# H0FR8.net
KiCad netlist of a schematic drawn in EAGLE
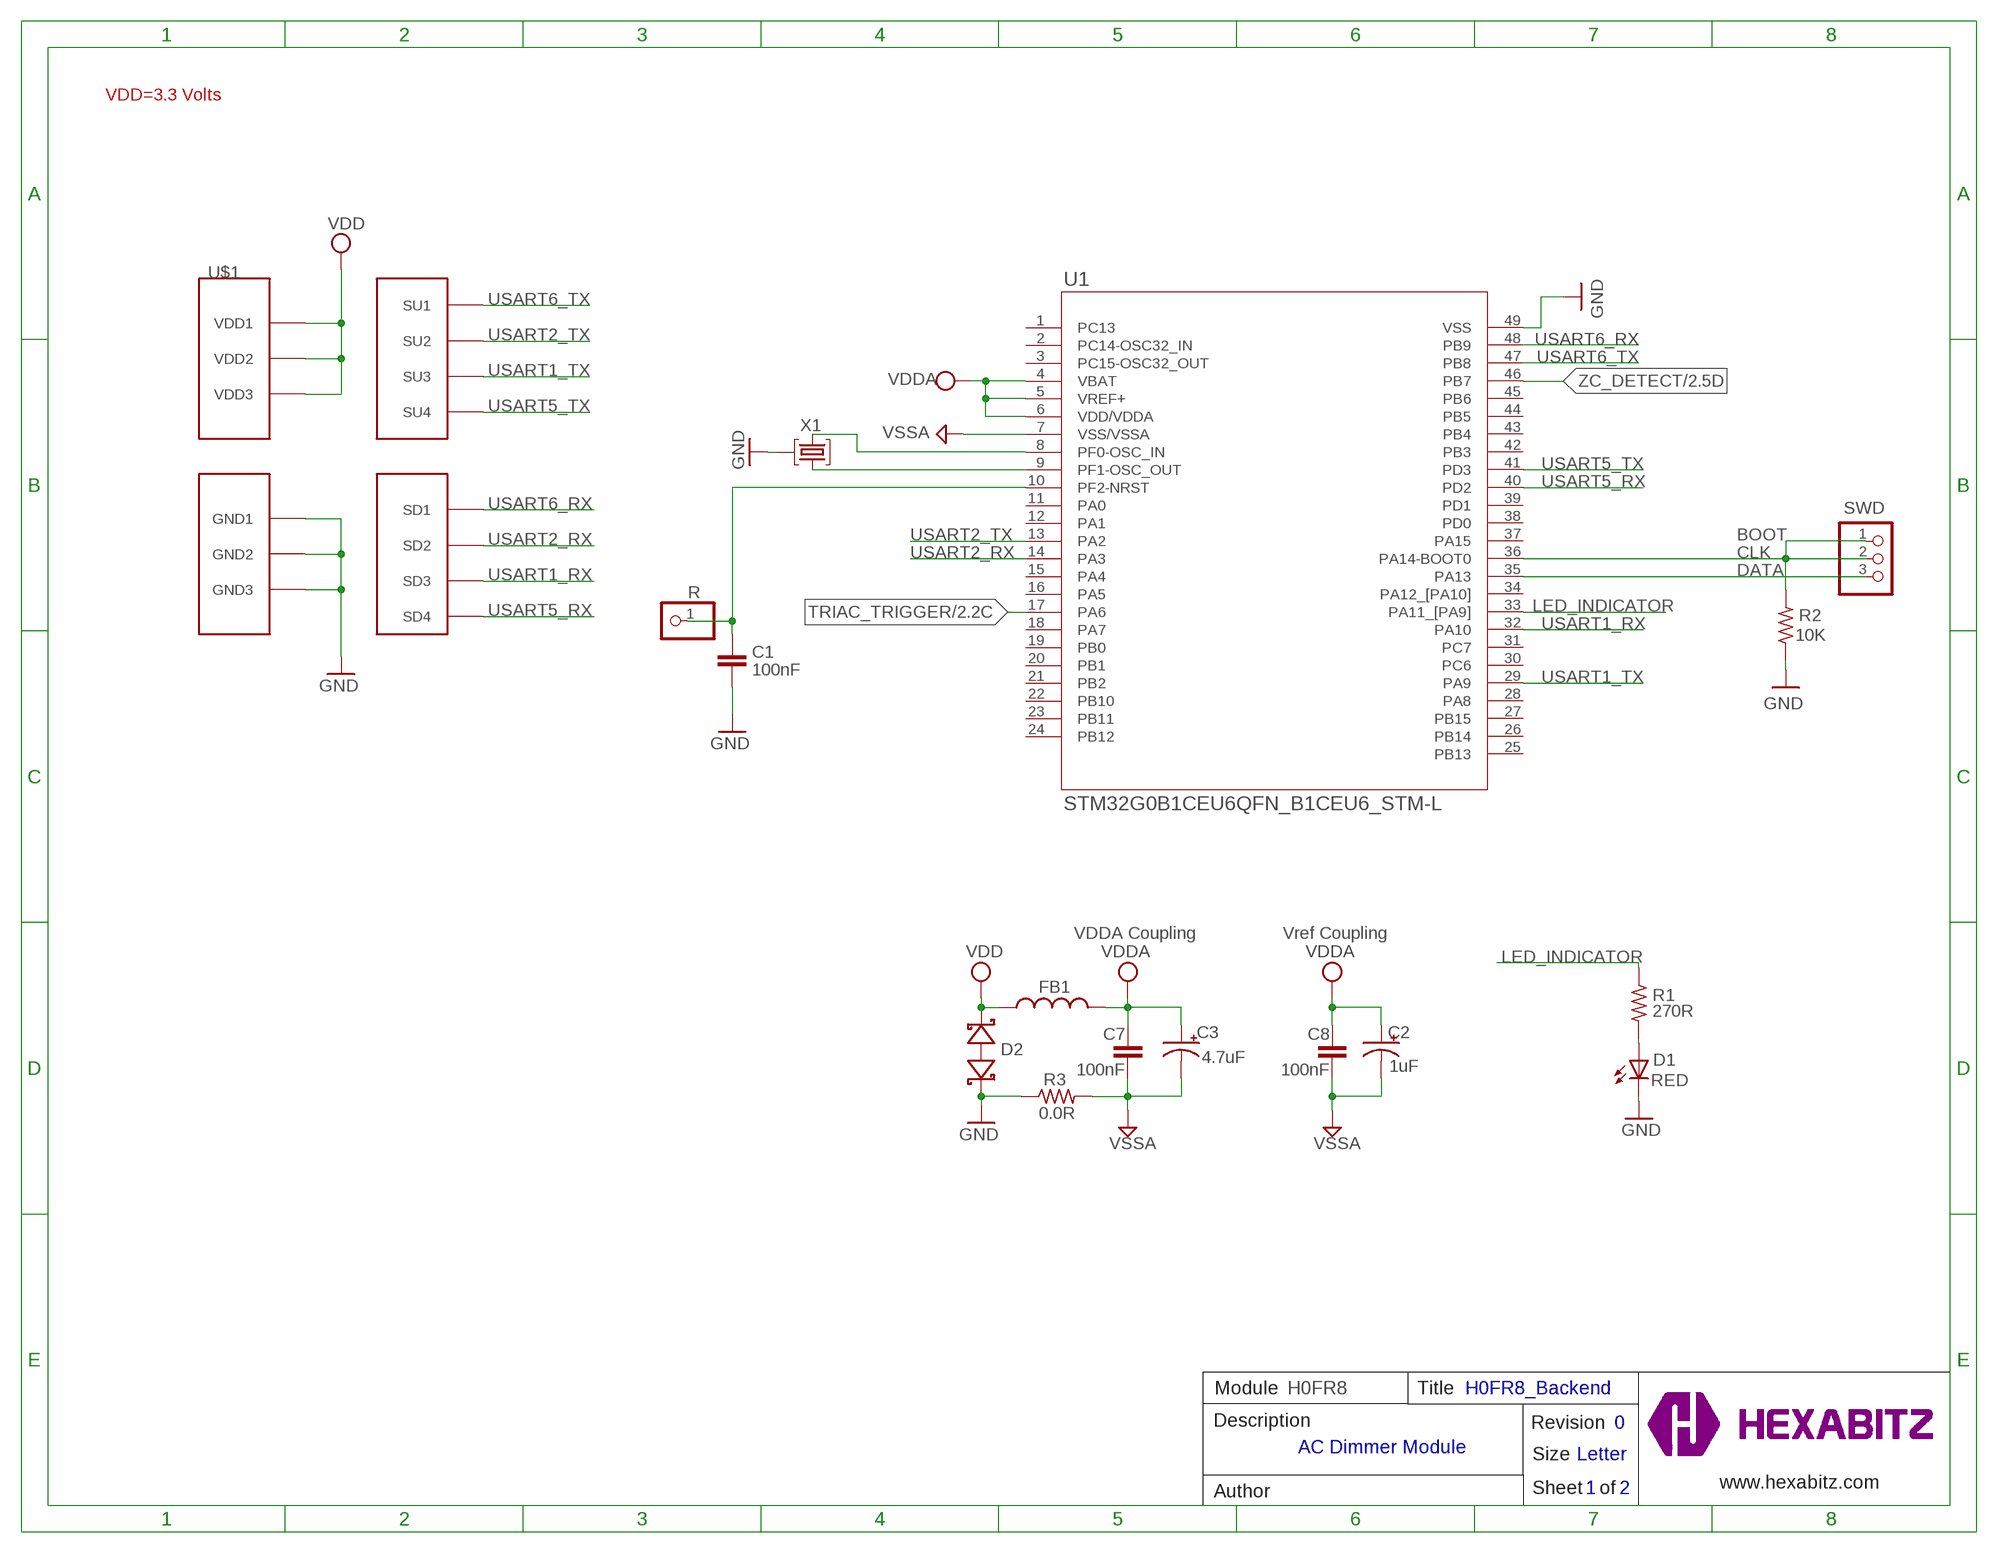
[diagram p0: schematic, sheet 1]
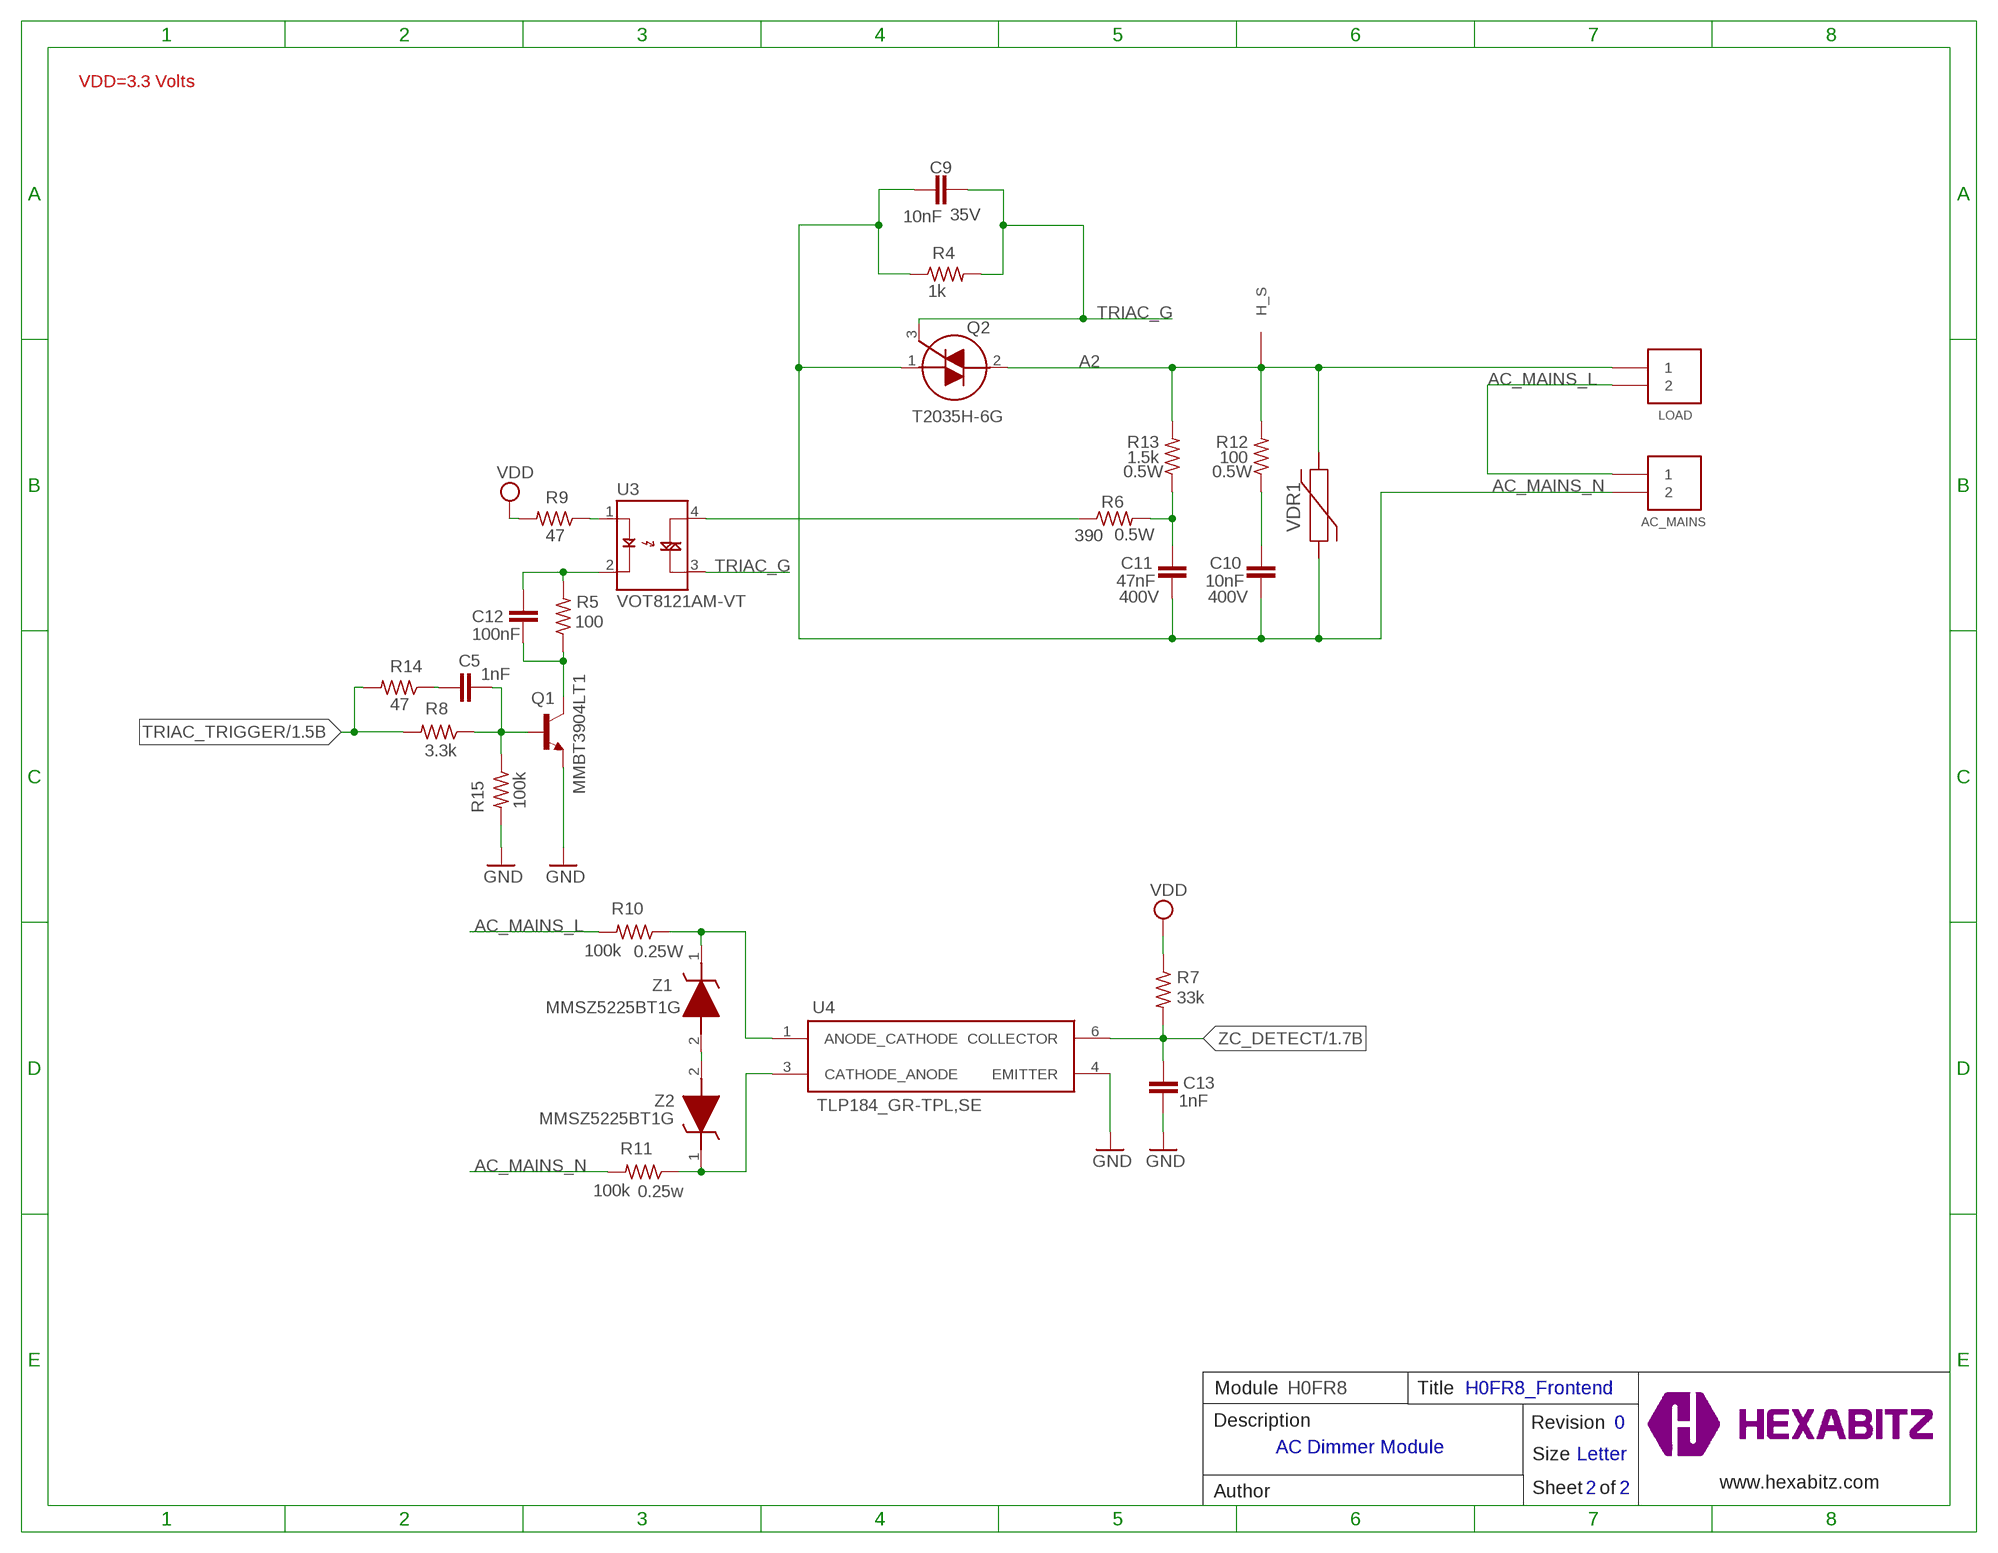
[diagram p1: schematic, sheet 2]

(export (version "E")
  (design (tool "Eeschema 10.0.6"))
  (components
    (comp (ref "AC_MAINS")
      (value "1546111-2")
      (footprint "eagle-import:1546111-2")
      (libsource (lib "eagle-import") (part "1546111-2"))
    )
    (comp (ref "C5")
      (value "1nF")
      (footprint "eagle-import:C-0603")
      (libsource (lib "eagle-import") (part "C-0603"))
    )
    (comp (ref "C9")
      (value "10nF")
      (footprint "eagle-import:C-0603")
      (fields (field (name "VOLTAGE_RATING") "35V"))
      (libsource (lib "eagle-import") (part "C-0603"))
    )
    (comp (ref "C10")
      (value "10nF")
      (footprint "eagle-import:C-0805")
      (fields (field (name "MPN") "C2012X7T2W103M085AA") (field (name "VOLTAGE_RATING") "400V"))
      (libsource (lib "eagle-import") (part "C-0805"))
    )
    (comp (ref "C11")
      (value "47nF")
      (footprint "eagle-import:C-0805")
      (fields (field (name "MPN") "C2012X7T2W473K125AA") (field (name "VOLTAGE_RATING") "400V"))
      (libsource (lib "eagle-import") (part "C-0805"))
    )
    (comp (ref "C12")
      (value "100nF")
      (footprint "eagle-import:C-0603")
      (libsource (lib "eagle-import") (part "C-0603"))
    )
    (comp (ref "C13")
      (value "1nF")
      (footprint "eagle-import:C-0603")
      (libsource (lib "eagle-import") (part "C-0603"))
    )
    (comp (ref "LOAD")
      (value "1546111-2")
      (footprint "eagle-import:1546111-2")
      (libsource (lib "eagle-import") (part "1546111-2"))
    )
    (comp (ref "Q1")
      (value "MMBT3904LT1")
      (footprint "eagle-import:MMBT3904LT1")
      (fields
        (field (name "MFN") "ON Semiconductor")
        (field (name "MPN") "MMBT3904LT1G")
        (field (name "OCTOPART_ID") "0bb6c2bc2200d471")
        (field (name "OCTOPART_URL") "http://octopart.com/mmbt3904lt1g-on+semiconductor-3280")
        (field (name "POLARITY") "NPN")
        (field (name "POWER_DISSIPATION") "0.225 W")
        (field (name "VOLTAGE_RATING_DC") "40.0 V")
      )
      (libsource (lib "eagle-import") (part "MMBT3904LT1"))
    )
    (comp (ref "Q2")
      (value "T2035H-6G")
      (footprint "eagle-import:T2035H6G")
      (fields (field (name "MOUSER_PART_NUMBER") "511-T2035H-6G"))
      (libsource (lib "eagle-import") (part "T2035H-6G"))
    )
    (comp (ref "R4")
      (value "1k")
      (footprint "eagle-import:R-0603")
      (libsource (lib "eagle-import") (part "R-0603"))
    )
    (comp (ref "R5")
      (value "100")
      (footprint "eagle-import:R-0603")
      (fields
        (field (name "MFN") "Yageo")
        (field (name "MPN") "RC0402FR-07100RL")
        (field (name "OCTOPART_URL") "https://octopart.com/crcw0603110rfkea-vishay-39455532")
        (field (name "RESISTANCE") "110.0 Ω")
        (field (name "TOLERANCE") "±1%")
      )
      (libsource (lib "eagle-import") (part "R-0603"))
    )
    (comp (ref "R6")
      (value "390")
      (footprint "eagle-import:R-0805")
      (fields (field (name "MPN") "ERJ-P06J391V") (field (name "POWER") "0.5W"))
      (libsource (lib "eagle-import") (part "R-0805"))
    )
    (comp (ref "R7")
      (value "33k")
      (footprint "eagle-import:R-0603")
      (fields
        (field (name "MFN") "Yageo")
        (field (name "MPN") "RC0402FR-07100RL")
        (field (name "OCTOPART_URL") "https://octopart.com/crcw0603110rfkea-vishay-39455532")
        (field (name "RESISTANCE") "110.0 Ω")
        (field (name "TOLERANCE") "±1%")
      )
      (libsource (lib "eagle-import") (part "R-0603"))
    )
    (comp (ref "R8")
      (value "3.3k")
      (footprint "eagle-import:R-0603")
      (fields
        (field (name "MFN") "Yageo")
        (field (name "MPN") "RC0603JR-070RL")
        (field (name "OCTOPART_URL") "https://octopart.com/crcw06032k40jnea-vishay-40298967")
        (field (name "RESISTANCE") "2400.0 Ω")
        (field (name "TOLERANCE") "±5%")
      )
      (libsource (lib "eagle-import") (part "R-0603"))
    )
    (comp (ref "R9")
      (value "47")
      (footprint "eagle-import:R-0603")
      (fields
        (field (name "MFN") "Yageo")
        (field (name "MPN") "RC0402FR-07100RL")
        (field (name "OCTOPART_URL") "https://octopart.com/crcw0603110rfkea-vishay-39455532")
        (field (name "RESISTANCE") "110.0 Ω")
        (field (name "TOLERANCE") "±1%")
      )
      (libsource (lib "eagle-import") (part "R-0603"))
    )
    (comp (ref "R10")
      (value "100k")
      (footprint "eagle-import:R-0805")
      (fields
        (field (name "MFN") "Yageo")
        (field (name "MPN") "RC0603JR-070RL")
        (field (name "OCTOPART_URL") "https://octopart.com/crcw06032k40jnea-vishay-40298967")
        (field (name "POWER") "0.25W")
        (field (name "RESISTANCE") "2400.0 Ω")
        (field (name "TOLERANCE") "±5%")
      )
      (libsource (lib "eagle-import") (part "R-0805"))
    )
    (comp (ref "R11")
      (value "100k")
      (footprint "eagle-import:R-0805")
      (fields (field (name "MPN") "ERJ-P06J104V") (field (name "POWER") "0.25w"))
      (libsource (lib "eagle-import") (part "R-0805"))
    )
    (comp (ref "R12")
      (value "100")
      (footprint "eagle-import:R-0805")
      (fields (field (name "MPN") "ERJ-P06J101V") (field (name "POWER") "0.5W"))
      (libsource (lib "eagle-import") (part "R-0805"))
    )
    (comp (ref "R13")
      (value "1.5k")
      (footprint "eagle-import:R-0805")
      (fields (field (name "MPN") "ERJ-P06J152V") (field (name "POWER") "0.5W"))
      (libsource (lib "eagle-import") (part "R-0805"))
    )
    (comp (ref "R14")
      (value "47")
      (footprint "eagle-import:R-0603")
      (fields
        (field (name "MFN") "Yageo")
        (field (name "MPN") "RC0402FR-07100RL")
        (field (name "OCTOPART_URL") "https://octopart.com/crcw0603110rfkea-vishay-39455532")
        (field (name "RESISTANCE") "110.0 Ω")
        (field (name "TOLERANCE") "±1%")
      )
      (libsource (lib "eagle-import") (part "R-0603"))
    )
    (comp (ref "R15")
      (value "100k")
      (footprint "eagle-import:R-0603")
      (fields
        (field (name "MFN") "Yageo")
        (field (name "MPN") "RC0603JR-070RL")
        (field (name "OCTOPART_URL") "https://octopart.com/crcw06032k40jnea-vishay-40298967")
        (field (name "RESISTANCE") "2400.0 Ω")
        (field (name "TOLERANCE") "±5%")
      )
      (libsource (lib "eagle-import") (part "R-0603"))
    )
    (comp (ref "U$2")
      (value "FK244D2PAK")
      (footprint "eagle-import:FK244D2PAK")
      (libsource (lib "eagle-import") (part "FK244D2PAK"))
    )
    (comp (ref "U3")
      (value "VOT8121AM-VT")
      (footprint "eagle-import:SOIC254P675X240-4N")
      (fields (field (name "MF") "Vishay Semiconductor Opto Division"))
      (libsource (lib "eagle-import") (part "VOT8121AM-VT"))
    )
    (comp (ref "U4")
      (value "TLP184_GR-TPL,SE")
      (footprint "eagle-import:SOIC254P700X230-4N")
      (libsource (lib "eagle-import") (part "TLP184_GR-TPL,SE"))
    )
    (comp (ref "VDR1")
      (value "V275LA4P")
      (footprint "eagle-import:LA_07MM_LOW_LTF")
      (fields (field (name "COPYRIGHT") "Copyright (C) 2024 Ultra Librarian. All rights reserved."))
      (libsource (lib "eagle-import") (part "V275LA4P"))
    )
    (comp (ref "Z1")
      (value "MMSZ5225BT1G")
      (footprint "eagle-import:SOD3716X135N")
      (fields (field (name "MOUSER_PART_NUMBER") "863-MMSZ5225BT1G"))
      (libsource (lib "eagle-import") (part "MMSZ5225BT1G"))
    )
    (comp (ref "Z2")
      (value "MMSZ5225BT1G")
      (footprint "eagle-import:SOD3716X135N")
      (fields (field (name "MOUSER_PART_NUMBER") "863-MMSZ5225BT1G"))
      (libsource (lib "eagle-import") (part "MMSZ5225BT1G"))
    )
    (comp (ref "C1")
      (value "100nF")
      (footprint "eagle-import:C-0603")
      (libsource (lib "eagle-import") (part "C-0603"))
    )
    (comp (ref "C2")
      (value "1uF")
      (footprint "eagle-import:C-0805-POL")
      (fields
        (field (name "CAPACITANCE") "1.00uF")
        (field (name "MFN") "Yageo")
        (field (name "MPN") "CC0805KKX7R7BB105")
        (field (name "OCTOPART_URL") "https://octopart.com/cc0805kkx7r7bb105-yageo-8376555?r=sp&s=YKl1wwtkROau_X5nniH2ig")
        (field (name "TOLERANCE") "10%")
        (field (name "VOLTAGE_RATING") "16V")
      )
      (libsource (lib "eagle-import") (part "C-0805-POL"))
    )
    (comp (ref "C3")
      (value "4.7uF")
      (footprint "eagle-import:C-0805-POL")
      (fields
        (field (name "CAPACITANCE") "4.7uF")
        (field (name "MFN") "Murata")
        (field (name "MPN") "GRM21BC81E475KA12L")
        (field (name "OCTOPART_URL") "https://octopart.com/grm21bc81e475ka12l-murata-10331911?r=sp&s=RY3qZSD8T6mG6TC9CHI5qQ")
        (field (name "TOLERANCE") "10%")
        (field (name "VOLTAGE_RATING") "25V")
      )
      (libsource (lib "eagle-import") (part "C-0805-POL"))
    )
    (comp (ref "C7")
      (value "100nF")
      (footprint "eagle-import:C-0603")
      (libsource (lib "eagle-import") (part "C-0603"))
    )
    (comp (ref "C8")
      (value "100nF")
      (footprint "eagle-import:C-0603")
      (libsource (lib "eagle-import") (part "C-0603"))
    )
    (comp (ref "D1")
      (value "RED")
      (footprint "eagle-import:VLMS1300-GS08")
      (fields
        (field (name "MPN") "VLMS1300-GS08")
        (field (name "MFN") "Vishay")
        (field (name "MPN_1") "VLMS1300-GS08")
        (field (name "OCTOPART_URL") "https://octopart.com/vlms1300-gs08-vishay-21709201?r=sp&s=_gcP4_q8T1SC6PJQPTQ9yA")
      )
      (libsource (lib "eagle-import") (part "VLMS1300-GS08"))
    )
    (comp (ref "D2")
      (value "BOURNS_CDSOD323-T03SCBOURNS_CDSOD323-T03SC_0_0")
      (footprint "eagle-import:BOURNS_CDSOD323-T03SC_0")
      (fields (field (name "MPN") "CDSOD323-T03SC"))
      (libsource (lib "eagle-import") (part "BOURNS_CDSOD323-T03SCBOURNS_CDSOD323-T03SC_0_0"))
    )
    (comp (ref "FB1")
      (value "FB-0603")
      (footprint "eagle-import:FB-0603")
      (libsource (lib "eagle-import") (part "FB-0603"))
    )
    (comp (ref "R")
      (value "R")
      (footprint "eagle-import:1X01")
      (fields (field (name "MPN") "87227-1"))
      (libsource (lib "eagle-import") (part "PINHD-1X1"))
    )
    (comp (ref "R1")
      (value "270R")
      (footprint "eagle-import:R-0603")
      (libsource (lib "eagle-import") (part "R-0603"))
    )
    (comp (ref "R2")
      (value "10K")
      (footprint "eagle-import:R-0603")
      (libsource (lib "eagle-import") (part "R-0603"))
    )
    (comp (ref "R3")
      (value "0.0R")
      (footprint "eagle-import:R-0603")
      (libsource (lib "eagle-import") (part "R-0603"))
    )
    (comp (ref "SWD")
      (value "PINHD-1X3")
      (footprint "eagle-import:1X03")
      (libsource (lib "eagle-import") (part "PINHD-1X3"))
    )
    (comp (ref "TRIMBLE-LOGO2")
      (value "HEXA-LOGO")
      (footprint "eagle-import:HEXA-LOGO")
      (libsource (lib "eagle-import") (part "HEXA-LOGO"))
    )
    (comp (ref "U$1")
      (value "HEXABIT_17.32_X3_NO_P1_P2_P3_P4_P5_P6_P11_P12")
      (footprint "eagle-import:HEXABIT_17.32_X3_NO_P1_P2_P3_P4_P5_P6_P11_P12")
      (libsource (lib "eagle-import") (part "HEXABIT_17.32_X3_NO_P1_P2_P3_P4_P5_P6_P11_P12"))
    )
    (comp (ref "U1")
      (value "STM32G0B1CEU6QFN_B1CEU6_STM-L")
      (footprint "eagle-import:QFN_B1CEU6_STM-L")
      (fields
        (field (name "MANUFACTURER_PART_NUMBER") "STM32G0B1CEU6")
        (field (name "COPYRIGHT") "Copyright (C) 2021 Ultra Librarian. All rights reserved.")
      )
      (libsource (lib "eagle-import") (part "STM32G0B1CEU6QFN_B1CEU6_STM-L"))
    )
    (comp (ref "X1")
      (value "XTALL_CSTCE8M00G52")
      (footprint "eagle-import:XTALL_CSTCE8M00G52")
      (fields (field (name "MPN") "CSTCE8M00G52Z-R0"))
      (libsource (lib "eagle-import") (part "XTALL_CSTCE8M00G52"))
    )
  )
  (nets
    (net (code "1") (name "A2") (class "Default")
      (node (ref "LOAD") (pin "1") (pinfunction "1_1") (pintype "power_in"))
      (node (ref "Q2") (pin "2") (pinfunction "MT2_2") (pintype "bidirectional"))
      (node (ref "R12") (pin "2") (pinfunction "2_2") (pintype "passive"))
      (node (ref "R13") (pin "2") (pinfunction "2_2") (pintype "passive"))
      (node (ref "U$2") (pin "P$1") (pinfunction "H_S_P$1") (pintype "bidirectional"))
      (node (ref "U$2") (pin "P$2") (pinfunction "H_S_P$2") (pintype "bidirectional"))
      (node (ref "VDR1") (pin "2") (pinfunction "2_2") (pintype "passive"))
    )
    (net (code "2") (name "AC_MAINS_L") (class "Default")
      (node (ref "AC_MAINS") (pin "1") (pinfunction "1_1") (pintype "power_in"))
      (node (ref "LOAD") (pin "2") (pinfunction "2_2") (pintype "power_in"))
      (node (ref "R10") (pin "2") (pinfunction "2_2") (pintype "passive"))
    )
    (net (code "3") (name "AC_MAINS_N") (class "Default")
      (node (ref "AC_MAINS") (pin "2") (pinfunction "2_2") (pintype "power_in"))
      (node (ref "C10") (pin "2") (pinfunction "2_2") (pintype "passive"))
      (node (ref "C11") (pin "2") (pinfunction "2_2") (pintype "passive"))
      (node (ref "C9") (pin "2") (pinfunction "2_2") (pintype "passive"))
      (node (ref "Q2") (pin "1") (pinfunction "MT1_1") (pintype "bidirectional"))
      (node (ref "R11") (pin "2") (pinfunction "2_2") (pintype "passive"))
      (node (ref "R4") (pin "1") (pinfunction "1_1") (pintype "passive"))
      (node (ref "VDR1") (pin "1") (pinfunction "1_1") (pintype "passive"))
    )
    (net (code "4") (name "CLK") (class "Default")
      (node (ref "R2") (pin "2") (pinfunction "2_2") (pintype "passive"))
      (node (ref "SWD") (pin "1") (pinfunction "1_1") (pintype "passive"))
      (node (ref "SWD") (pin "2") (pinfunction "2_2") (pintype "passive"))
      (node (ref "U1") (pin "36") (pinfunction "PA14-BOOT0_36") (pintype "bidirectional"))
    )
    (net (code "5") (name "DATA") (class "Default")
      (node (ref "SWD") (pin "3") (pinfunction "3_3") (pintype "passive"))
      (node (ref "U1") (pin "35") (pinfunction "PA13_35") (pintype "bidirectional"))
    )
    (net (code "6") (name "GND") (class "Default")
      (node (ref "C1") (pin "2") (pinfunction "2_2") (pintype "passive"))
      (node (ref "C13") (pin "2") (pinfunction "2_2") (pintype "passive"))
      (node (ref "D1") (pin "C") (pinfunction "C_C") (pintype "passive"))
      (node (ref "D2") (pin "2") (pinfunction "C_2") (pintype "passive"))
      (node (ref "Q1") (pin "2") (pinfunction "E_2") (pintype "passive"))
      (node (ref "R15") (pin "2") (pinfunction "2_2") (pintype "passive"))
      (node (ref "R2") (pin "1") (pinfunction "1_1") (pintype "passive"))
      (node (ref "R3") (pin "1") (pinfunction "1_1") (pintype "passive"))
      (node (ref "U$1") (pin "PAD_PD12") (pinfunction "GND1_PAD_PD12") (pintype "power_in"))
      (node (ref "U$1") (pin "PAD_PD17") (pinfunction "GND2_PAD_PD17") (pintype "power_in"))
      (node (ref "U$1") (pin "PAD_PD19") (pinfunction "GND3_PAD_PD19") (pintype "power_in"))
      (node (ref "U1") (pin "49") (pinfunction "VSS_49") (pintype "passive"))
      (node (ref "U4") (pin "4") (pinfunction "EMITTER_4") (pintype "bidirectional"))
      (node (ref "X1") (pin "P$2") (pinfunction "2_P$2") (pintype "passive"))
    )
    (net (code "7") (name "LED_INDICATOR") (class "Default")
      (node (ref "R1") (pin "1") (pinfunction "1_1") (pintype "passive"))
      (node (ref "U1") (pin "33") (pinfunction "PA11_[PA9]_33") (pintype "bidirectional"))
    )
    (net (code "8") (name "Net-(C5-Pad2)") (class "Default")
      (node (ref "C5") (pin "2") (pinfunction "2_2") (pintype "passive"))
      (node (ref "R14") (pin "1") (pinfunction "1_1") (pintype "passive"))
    )
    (net (code "9") (name "Net-(C10-Pad1)") (class "Default")
      (node (ref "C10") (pin "1") (pinfunction "1_1") (pintype "passive"))
      (node (ref "R12") (pin "1") (pinfunction "1_1") (pintype "passive"))
    )
    (net (code "10") (name "Net-(C11-Pad1)") (class "Default")
      (node (ref "C11") (pin "1") (pinfunction "1_1") (pintype "passive"))
      (node (ref "R13") (pin "1") (pinfunction "1_1") (pintype "passive"))
      (node (ref "R6") (pin "2") (pinfunction "2_2") (pintype "passive"))
    )
    (net (code "11") (name "Net-(D1-PadA)") (class "Default")
      (node (ref "D1") (pin "A") (pinfunction "A_A") (pintype "passive"))
      (node (ref "R1") (pin "2") (pinfunction "2_2") (pintype "passive"))
    )
    (net (code "12") (name "Net-(Q1-B)") (class "Default")
      (node (ref "C5") (pin "1") (pinfunction "1_1") (pintype "passive"))
      (node (ref "Q1") (pin "1") (pinfunction "B_1") (pintype "passive"))
      (node (ref "R15") (pin "1") (pinfunction "1_1") (pintype "passive"))
      (node (ref "R8") (pin "1") (pinfunction "1_1") (pintype "passive"))
    )
    (net (code "13") (name "Net-(Q1-C)") (class "Default")
      (node (ref "C12") (pin "2") (pinfunction "2_2") (pintype "passive"))
      (node (ref "Q1") (pin "3") (pinfunction "C_3") (pintype "passive"))
      (node (ref "R5") (pin "1") (pinfunction "1_1") (pintype "passive"))
    )
    (net (code "14") (name "Net-(U1-PF0-OSC_IN)") (class "Default")
      (node (ref "U1") (pin "8") (pinfunction "PF0-OSC_IN_8") (pintype "bidirectional"))
      (node (ref "X1") (pin "P$3") (pinfunction "3_P$3") (pintype "passive"))
    )
    (net (code "15") (name "Net-(U1-PF1-OSC_OUT)") (class "Default")
      (node (ref "U1") (pin "9") (pinfunction "PF1-OSC_OUT_9") (pintype "output"))
      (node (ref "X1") (pin "P$1") (pinfunction "1_P$1") (pintype "passive"))
    )
    (net (code "16") (name "Net-(U1-PF2-NRST)") (class "Default")
      (node (ref "C1") (pin "1") (pinfunction "1_1") (pintype "passive"))
      (node (ref "R") (pin "1") (pinfunction "1_1") (pintype "passive"))
      (node (ref "U1") (pin "10") (pinfunction "PF2-NRST_10") (pintype "bidirectional"))
    )
    (net (code "17") (name "Net-(U3-A)") (class "Default")
      (node (ref "R9") (pin "1") (pinfunction "1_1") (pintype "passive"))
      (node (ref "U3") (pin "1") (pinfunction "A_1") (pintype "passive"))
    )
    (net (code "18") (name "Net-(U3-C)") (class "Default")
      (node (ref "C12") (pin "1") (pinfunction "1_1") (pintype "passive"))
      (node (ref "R5") (pin "2") (pinfunction "2_2") (pintype "passive"))
      (node (ref "U3") (pin "2") (pinfunction "C_2") (pintype "passive"))
    )
    (net (code "19") (name "Net-(U3-MT2)") (class "Default")
      (node (ref "R6") (pin "1") (pinfunction "1_1") (pintype "passive"))
      (node (ref "U3") (pin "4") (pinfunction "MT2_4") (pintype "passive"))
    )
    (net (code "20") (name "Net-(U4-ANODE_CATHODE)") (class "Default")
      (node (ref "R10") (pin "1") (pinfunction "1_1") (pintype "passive"))
      (node (ref "U4") (pin "1") (pinfunction "ANODE_CATHODE_1") (pintype "bidirectional"))
      (node (ref "Z1") (pin "1") (pinfunction "K_1") (pintype "bidirectional"))
    )
    (net (code "21") (name "Net-(U4-CATHODE_ANODE)") (class "Default")
      (node (ref "R11") (pin "1") (pinfunction "1_1") (pintype "passive"))
      (node (ref "U4") (pin "3") (pinfunction "CATHODE_ANODE_3") (pintype "bidirectional"))
      (node (ref "Z2") (pin "1") (pinfunction "K_1") (pintype "bidirectional"))
    )
    (net (code "22") (name "Net-(Z1-A)") (class "Default")
      (node (ref "Z1") (pin "2") (pinfunction "A_2") (pintype "bidirectional"))
      (node (ref "Z2") (pin "2") (pinfunction "A_2") (pintype "bidirectional"))
    )
    (net (code "23") (name "TRIAC_G") (class "Default")
      (node (ref "C9") (pin "1") (pinfunction "1_1") (pintype "passive"))
      (node (ref "Q2") (pin "3") (pinfunction "G_3") (pintype "bidirectional"))
      (node (ref "R4") (pin "2") (pinfunction "2_2") (pintype "passive"))
      (node (ref "U3") (pin "3") (pinfunction "MT1_3") (pintype "passive"))
    )
    (net (code "24") (name "TRIAC_TRIGGER") (class "Default")
      (node (ref "R14") (pin "2") (pinfunction "2_2") (pintype "passive"))
      (node (ref "R8") (pin "2") (pinfunction "2_2") (pintype "passive"))
      (node (ref "U1") (pin "17") (pinfunction "PA6_17") (pintype "bidirectional"))
    )
    (net (code "25") (name "USART1_RX") (class "Default")
      (node (ref "U$1") (pin "PAD_PD2") (pinfunction "SD3_PAD_PD2") (pintype "bidirectional"))
      (node (ref "U1") (pin "32") (pinfunction "PA10_32") (pintype "bidirectional"))
    )
    (net (code "26") (name "USART1_TX") (class "Default")
      (node (ref "U$1") (pin "PAD_PU2") (pinfunction "SU3_PAD_PU2") (pintype "bidirectional"))
      (node (ref "U1") (pin "29") (pinfunction "PA9_29") (pintype "bidirectional"))
    )
    (net (code "27") (name "USART2_RX") (class "Default")
      (node (ref "U$1") (pin "PAD_PD1") (pinfunction "SD2_PAD_PD1") (pintype "bidirectional"))
      (node (ref "U1") (pin "14") (pinfunction "PA3_14") (pintype "bidirectional"))
    )
    (net (code "28") (name "USART2_TX") (class "Default")
      (node (ref "U$1") (pin "PAD_PU1") (pinfunction "SU2_PAD_PU1") (pintype "bidirectional"))
      (node (ref "U1") (pin "13") (pinfunction "PA2_13") (pintype "bidirectional"))
    )
    (net (code "29") (name "USART5_RX") (class "Default")
      (node (ref "U$1") (pin "PAD_PD8") (pinfunction "SD4_PAD_PD8") (pintype "bidirectional"))
      (node (ref "U1") (pin "40") (pinfunction "PD2_40") (pintype "bidirectional"))
    )
    (net (code "30") (name "USART5_TX") (class "Default")
      (node (ref "U$1") (pin "PAD_PU8") (pinfunction "SU4_PAD_PU8") (pintype "bidirectional"))
      (node (ref "U1") (pin "41") (pinfunction "PD3_41") (pintype "bidirectional"))
    )
    (net (code "31") (name "USART6_RX") (class "Default")
      (node (ref "U$1") (pin "PAD_PD3") (pinfunction "SD1_PAD_PD3") (pintype "bidirectional"))
      (node (ref "U1") (pin "48") (pinfunction "PB9_48") (pintype "bidirectional"))
    )
    (net (code "32") (name "USART6_TX") (class "Default")
      (node (ref "U$1") (pin "PAD_PU3") (pinfunction "SU1_PAD_PU3") (pintype "bidirectional"))
      (node (ref "U1") (pin "47") (pinfunction "PB8_47") (pintype "bidirectional"))
    )
    (net (code "33") (name "VDD") (class "Default")
      (node (ref "D2") (pin "1") (pinfunction "A_1") (pintype "passive"))
      (node (ref "FB1") (pin "1") (pinfunction "1_1") (pintype "passive"))
      (node (ref "R7") (pin "1") (pinfunction "1_1") (pintype "passive"))
      (node (ref "R9") (pin "2") (pinfunction "2_2") (pintype "passive"))
      (node (ref "U$1") (pin "PAD_PU12") (pinfunction "VDD1_PAD_PU12") (pintype "power_in"))
      (node (ref "U$1") (pin "PAD_PU17") (pinfunction "VDD2_PAD_PU17") (pintype "power_in"))
      (node (ref "U$1") (pin "PAD_PU19") (pinfunction "VDD3_PAD_PU19") (pintype "power_in"))
    )
    (net (code "34") (name "VDDA") (class "Default")
      (node (ref "C2") (pin "1") (pinfunction "+_1") (pintype "passive"))
      (node (ref "C3") (pin "1") (pinfunction "+_1") (pintype "passive"))
      (node (ref "C7") (pin "1") (pinfunction "1_1") (pintype "passive"))
      (node (ref "C8") (pin "1") (pinfunction "1_1") (pintype "passive"))
      (node (ref "FB1") (pin "2") (pinfunction "2_2") (pintype "passive"))
      (node (ref "U1") (pin "4") (pinfunction "VBAT_4") (pintype "passive"))
      (node (ref "U1") (pin "5") (pinfunction "VREF+_5") (pintype "power_in"))
      (node (ref "U1") (pin "6") (pinfunction "VDD/VDDA_6") (pintype "power_in"))
    )
    (net (code "35") (name "VSSA") (class "Default")
      (node (ref "C2") (pin "2") (pinfunction "-_2") (pintype "passive"))
      (node (ref "C3") (pin "2") (pinfunction "-_2") (pintype "passive"))
      (node (ref "C7") (pin "2") (pinfunction "2_2") (pintype "passive"))
      (node (ref "C8") (pin "2") (pinfunction "2_2") (pintype "passive"))
      (node (ref "R3") (pin "2") (pinfunction "2_2") (pintype "passive"))
      (node (ref "U1") (pin "7") (pinfunction "VSS/VSSA_7") (pintype "passive"))
    )
    (net (code "36") (name "ZC_DETECT") (class "Default")
      (node (ref "C13") (pin "1") (pinfunction "1_1") (pintype "passive"))
      (node (ref "R7") (pin "2") (pinfunction "2_2") (pintype "passive"))
      (node (ref "U1") (pin "46") (pinfunction "PB7_46") (pintype "bidirectional"))
      (node (ref "U4") (pin "6") (pinfunction "COLLECTOR_6") (pintype "bidirectional"))
    )
    (net (code "37") (name "unconnected-(U1-PA0-Pad11)") (class "Default")
      (node (ref "U1") (pin "11") (pinfunction "PA0_11") (pintype "bidirectional"))
    )
    (net (code "38") (name "unconnected-(U1-PA1-Pad12)") (class "Default")
      (node (ref "U1") (pin "12") (pinfunction "PA1_12") (pintype "bidirectional"))
    )
    (net (code "39") (name "unconnected-(U1-PA4-Pad15)") (class "Default")
      (node (ref "U1") (pin "15") (pinfunction "PA4_15") (pintype "bidirectional"))
    )
    (net (code "40") (name "unconnected-(U1-PA5-Pad16)") (class "Default")
      (node (ref "U1") (pin "16") (pinfunction "PA5_16") (pintype "bidirectional"))
    )
    (net (code "41") (name "unconnected-(U1-PA7-Pad18)") (class "Default")
      (node (ref "U1") (pin "18") (pinfunction "PA7_18") (pintype "bidirectional"))
    )
    (net (code "42") (name "unconnected-(U1-PA8-Pad28)") (class "Default")
      (node (ref "U1") (pin "28") (pinfunction "PA8_28") (pintype "bidirectional"))
    )
    (net (code "43") (name "unconnected-(U1-PA12_[PA10]-Pad34)") (class "Default")
      (node (ref "U1") (pin "34") (pinfunction "PA12_[PA10]_34") (pintype "bidirectional"))
    )
    (net (code "44") (name "unconnected-(U1-PA15-Pad37)") (class "Default")
      (node (ref "U1") (pin "37") (pinfunction "PA15_37") (pintype "bidirectional"))
    )
    (net (code "45") (name "unconnected-(U1-PB0-Pad19)") (class "Default")
      (node (ref "U1") (pin "19") (pinfunction "PB0_19") (pintype "bidirectional"))
    )
    (net (code "46") (name "unconnected-(U1-PB1-Pad20)") (class "Default")
      (node (ref "U1") (pin "20") (pinfunction "PB1_20") (pintype "bidirectional"))
    )
    (net (code "47") (name "unconnected-(U1-PB2-Pad21)") (class "Default")
      (node (ref "U1") (pin "21") (pinfunction "PB2_21") (pintype "bidirectional"))
    )
    (net (code "48") (name "unconnected-(U1-PB3-Pad42)") (class "Default")
      (node (ref "U1") (pin "42") (pinfunction "PB3_42") (pintype "bidirectional"))
    )
    (net (code "49") (name "unconnected-(U1-PB4-Pad43)") (class "Default")
      (node (ref "U1") (pin "43") (pinfunction "PB4_43") (pintype "bidirectional"))
    )
    (net (code "50") (name "unconnected-(U1-PB5-Pad44)") (class "Default")
      (node (ref "U1") (pin "44") (pinfunction "PB5_44") (pintype "bidirectional"))
    )
    (net (code "51") (name "unconnected-(U1-PB6-Pad45)") (class "Default")
      (node (ref "U1") (pin "45") (pinfunction "PB6_45") (pintype "bidirectional"))
    )
    (net (code "52") (name "unconnected-(U1-PB10-Pad22)") (class "Default")
      (node (ref "U1") (pin "22") (pinfunction "PB10_22") (pintype "bidirectional"))
    )
    (net (code "53") (name "unconnected-(U1-PB11-Pad23)") (class "Default")
      (node (ref "U1") (pin "23") (pinfunction "PB11_23") (pintype "bidirectional"))
    )
    (net (code "54") (name "unconnected-(U1-PB12-Pad24)") (class "Default")
      (node (ref "U1") (pin "24") (pinfunction "PB12_24") (pintype "bidirectional"))
    )
    (net (code "55") (name "unconnected-(U1-PB13-Pad25)") (class "Default")
      (node (ref "U1") (pin "25") (pinfunction "PB13_25") (pintype "bidirectional"))
    )
    (net (code "56") (name "unconnected-(U1-PB14-Pad26)") (class "Default")
      (node (ref "U1") (pin "26") (pinfunction "PB14_26") (pintype "bidirectional"))
    )
    (net (code "57") (name "unconnected-(U1-PB15-Pad27)") (class "Default")
      (node (ref "U1") (pin "27") (pinfunction "PB15_27") (pintype "bidirectional"))
    )
    (net (code "58") (name "unconnected-(U1-PC6-Pad30)") (class "Default")
      (node (ref "U1") (pin "30") (pinfunction "PC6_30") (pintype "bidirectional"))
    )
    (net (code "59") (name "unconnected-(U1-PC7-Pad31)") (class "Default")
      (node (ref "U1") (pin "31") (pinfunction "PC7_31") (pintype "bidirectional"))
    )
    (net (code "60") (name "unconnected-(U1-PC13-Pad1)") (class "Default")
      (node (ref "U1") (pin "1") (pinfunction "PC13_1") (pintype "bidirectional"))
    )
    (net (code "61") (name "unconnected-(U1-PC14-OSC32_IN-Pad2)") (class "Default")
      (node (ref "U1") (pin "2") (pinfunction "PC14-OSC32_IN_2") (pintype "bidirectional"))
    )
    (net (code "62") (name "unconnected-(U1-PC15-OSC32_OUT-Pad3)") (class "Default")
      (node (ref "U1") (pin "3") (pinfunction "PC15-OSC32_OUT_3") (pintype "output"))
    )
    (net (code "63") (name "unconnected-(U1-PD0-Pad38)") (class "Default")
      (node (ref "U1") (pin "38") (pinfunction "PD0_38") (pintype "bidirectional"))
    )
    (net (code "64") (name "unconnected-(U1-PD1-Pad39)") (class "Default")
      (node (ref "U1") (pin "39") (pinfunction "PD1_39") (pintype "bidirectional"))
    )
  )
)
